# main.net
KiCad netlist of a schematic drawn in EAGLE
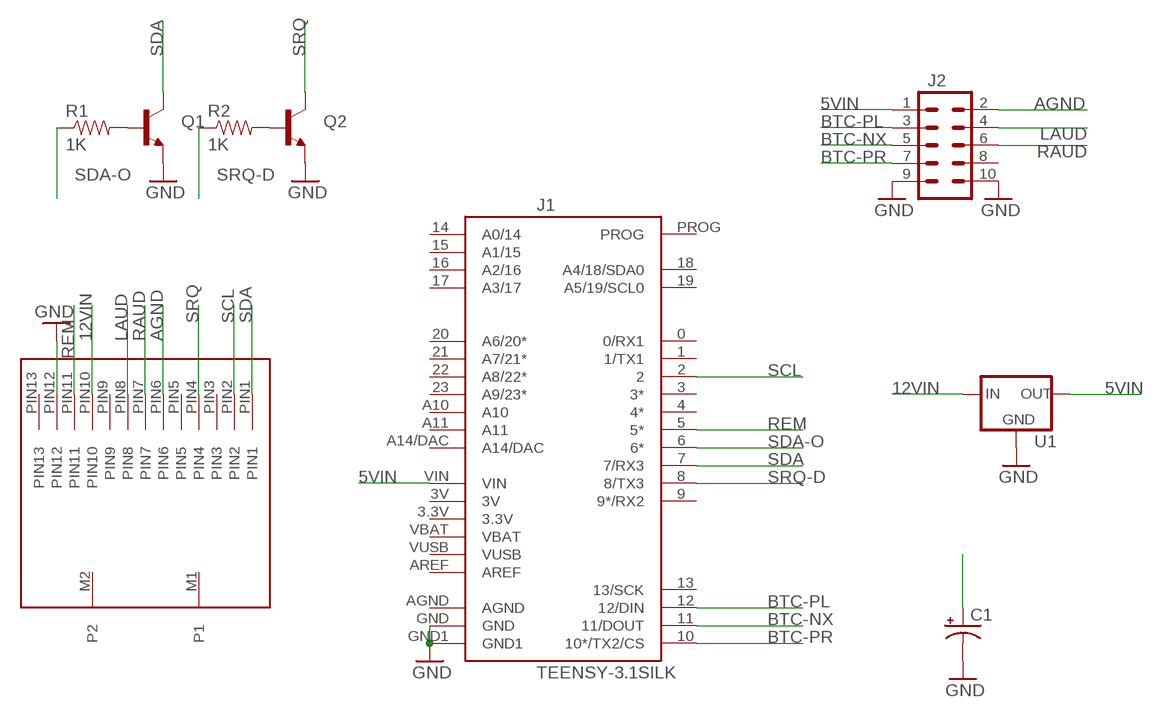
[diagram p0: schematic, sheet 1]

(export (version "E")
  (design (tool "Eeschema 10.0.6"))
  (components
    (comp (ref "C1")
      (value "10UF-25V-20%(PTH)")
      (footprint "eagle-import:CPOL-RADIAL-10UF-25V")
      (libsource (lib "eagle-import") (part "10UF-25V-20%(PTH)"))
    )
    (comp (ref "J1")
      (value "TEENSY-3.1SILK")
      (footprint "eagle-import:TEENSY-3.1")
      (libsource (lib "eagle-import") (part "TEENSY-3.1SILK"))
    )
    (comp (ref "J2")
      (value "M05X2NO_SILK")
      (footprint "eagle-import:2X5_NOSILK")
      (libsource (lib "eagle-import") (part "M05X2NO_SILK"))
    )
    (comp (ref "Q1")
      (value "TRANSISTOR_NPN2N3904")
      (footprint "eagle-import:TO-92")
      (libsource (lib "eagle-import") (part "TRANSISTOR_NPN2N3904"))
    )
    (comp (ref "Q2")
      (value "TRANSISTOR_NPN2N3904")
      (footprint "eagle-import:TO-92")
      (libsource (lib "eagle-import") (part "TRANSISTOR_NPN2N3904"))
    )
    (comp (ref "R1")
      (value "1K")
      (footprint "eagle-import:AXIAL-0.3")
      (libsource (lib "eagle-import") (part "1KOHM-1/4W-1%(PTH)"))
    )
    (comp (ref "R2")
      (value "1K")
      (footprint "eagle-import:AXIAL-0.3")
      (libsource (lib "eagle-import") (part "1KOHM-1/4W-1%(PTH)"))
    )
    (comp (ref "U$1")
      (value "13-DIN13PINDIN")
      (footprint "eagle-import:DIN-13")
      (libsource (lib "eagle-import") (part "13-DIN13PINDIN"))
    )
    (comp (ref "U1")
      (value "V_REG_78XX-TO-220")
      (footprint "eagle-import:TO-220-ALT")
      (libsource (lib "eagle-import") (part "V_REG_78XX-TO-220"))
    )
  )
  (nets
    (net (code "1") (name "/5VIN") (class "Default")
      (node (ref "C1") (pin "1") (pinfunction "+_1") (pintype "passive"))
      (node (ref "J1") (pin "VIN") (pinfunction "VIN_VIN") (pintype "bidirectional"))
      (node (ref "J2") (pin "1") (pinfunction "1_1") (pintype "passive"))
      (node (ref "U1") (pin "OUT") (pinfunction "OUT_OUT") (pintype "passive"))
    )
    (net (code "2") (name "/12VIN") (class "Default")
      (node (ref "U$1") (pin "PIN10") (pinfunction "PIN10_PIN10") (pintype "bidirectional"))
      (node (ref "U1") (pin "IN") (pinfunction "IN_IN") (pintype "input"))
    )
    (net (code "3") (name "/AGND") (class "Default")
      (node (ref "J2") (pin "2") (pinfunction "2_2") (pintype "passive"))
      (node (ref "U$1") (pin "PIN6") (pinfunction "PIN6_PIN6") (pintype "bidirectional"))
    )
    (net (code "4") (name "/BTC-NX") (class "Default")
      (node (ref "J1") (pin "11") (pinfunction "11/DOUT_11") (pintype "bidirectional"))
      (node (ref "J2") (pin "5") (pinfunction "5_5") (pintype "passive"))
    )
    (net (code "5") (name "/BTC-PL") (class "Default")
      (node (ref "J1") (pin "12") (pinfunction "12/DIN_12") (pintype "bidirectional"))
      (node (ref "J2") (pin "3") (pinfunction "3_3") (pintype "passive"))
    )
    (net (code "6") (name "/BTC-PR") (class "Default")
      (node (ref "J1") (pin "10") (pinfunction "10*/TX2/CS_10") (pintype "bidirectional"))
      (node (ref "J2") (pin "7") (pinfunction "7_7") (pintype "passive"))
    )
    (net (code "7") (name "/LAUD") (class "Default")
      (node (ref "J2") (pin "4") (pinfunction "4_4") (pintype "passive"))
      (node (ref "U$1") (pin "PIN8") (pinfunction "PIN8_PIN8") (pintype "bidirectional"))
    )
    (net (code "8") (name "/RAUD") (class "Default")
      (node (ref "J2") (pin "6") (pinfunction "6_6") (pintype "passive"))
      (node (ref "U$1") (pin "PIN7") (pinfunction "PIN7_PIN7") (pintype "bidirectional"))
    )
    (net (code "9") (name "/REM") (class "Default")
      (node (ref "J1") (pin "5") (pinfunction "5*_5") (pintype "bidirectional"))
      (node (ref "U$1") (pin "PIN11") (pinfunction "PIN11_PIN11") (pintype "bidirectional"))
    )
    (net (code "10") (name "/SCL") (class "Default")
      (node (ref "J1") (pin "2") (pinfunction "2_2") (pintype "bidirectional"))
      (node (ref "U$1") (pin "PIN2") (pinfunction "PIN2_PIN2") (pintype "bidirectional"))
    )
    (net (code "11") (name "/SDA") (class "Default")
      (node (ref "J1") (pin "7") (pinfunction "7/RX3_7") (pintype "bidirectional"))
      (node (ref "Q1") (pin "3") (pinfunction "C_3") (pintype "passive"))
      (node (ref "U$1") (pin "PIN1") (pinfunction "PIN1_PIN1") (pintype "bidirectional"))
    )
    (net (code "12") (name "/SDA-O") (class "Default")
      (node (ref "J1") (pin "6") (pinfunction "6*_6") (pintype "bidirectional"))
      (node (ref "R1") (pin "P$1") (pinfunction "1_P$1") (pintype "passive"))
    )
    (net (code "13") (name "/SRQ") (class "Default")
      (node (ref "Q2") (pin "3") (pinfunction "C_3") (pintype "passive"))
      (node (ref "U$1") (pin "PIN4") (pinfunction "PIN4_PIN4") (pintype "bidirectional"))
    )
    (net (code "14") (name "/SRQ-D") (class "Default")
      (node (ref "J1") (pin "8") (pinfunction "8/TX3_8") (pintype "bidirectional"))
      (node (ref "R2") (pin "P$1") (pinfunction "1_P$1") (pintype "passive"))
    )
    (net (code "15") (name "GND") (class "Default")
      (node (ref "C1") (pin "2") (pinfunction "-_2") (pintype "passive"))
      (node (ref "J1") (pin "GND") (pinfunction "GND_GND") (pintype "bidirectional"))
      (node (ref "J1") (pin "GND1") (pinfunction "GND1_GND1") (pintype "bidirectional"))
      (node (ref "J2") (pin "10") (pinfunction "10_10") (pintype "passive"))
      (node (ref "J2") (pin "9") (pinfunction "9_9") (pintype "passive"))
      (node (ref "Q1") (pin "1") (pinfunction "E_1") (pintype "passive"))
      (node (ref "Q2") (pin "1") (pinfunction "E_1") (pintype "passive"))
      (node (ref "U$1") (pin "PIN12") (pinfunction "PIN12_PIN12") (pintype "bidirectional"))
      (node (ref "U1") (pin "GND") (pinfunction "GND_GND") (pintype "input"))
    )
    (net (code "16") (name "Net-(Q1-B)") (class "Default")
      (node (ref "Q1") (pin "2") (pinfunction "B_2") (pintype "passive"))
      (node (ref "R1") (pin "P$2") (pinfunction "2_P$2") (pintype "passive"))
    )
    (net (code "17") (name "Net-(Q2-B)") (class "Default")
      (node (ref "Q2") (pin "2") (pinfunction "B_2") (pintype "passive"))
      (node (ref "R2") (pin "P$2") (pinfunction "2_P$2") (pintype "passive"))
    )
    (net (code "18") (name "unconnected-(J1-0{slash}RX1-Pad0)") (class "Default")
      (node (ref "J1") (pin "0") (pinfunction "0/RX1_0") (pintype "bidirectional"))
    )
    (net (code "19") (name "unconnected-(J1-1{slash}TX1-Pad1)") (class "Default")
      (node (ref "J1") (pin "1") (pinfunction "1/TX1_1") (pintype "bidirectional"))
    )
    (net (code "20") (name "unconnected-(J1-3*-Pad3)") (class "Default")
      (node (ref "J1") (pin "3") (pinfunction "3*_3") (pintype "bidirectional"))
    )
    (net (code "21") (name "unconnected-(J1-4*-Pad4)") (class "Default")
      (node (ref "J1") (pin "4") (pinfunction "4*_4") (pintype "bidirectional"))
    )
    (net (code "22") (name "unconnected-(J1-9*{slash}RX2-Pad9)") (class "Default")
      (node (ref "J1") (pin "9") (pinfunction "9*/RX2_9") (pintype "bidirectional"))
    )
    (net (code "23") (name "unconnected-(J1-13{slash}SCK-Pad13)") (class "Default")
      (node (ref "J1") (pin "13") (pinfunction "13/SCK_13") (pintype "bidirectional"))
    )
    (net (code "24") (name "unconnected-(J1-A0{slash}14-Pad14)") (class "Default")
      (node (ref "J1") (pin "14") (pinfunction "A0/14_14") (pintype "bidirectional"))
    )
    (net (code "25") (name "unconnected-(J1-A1{slash}15-Pad15)") (class "Default")
      (node (ref "J1") (pin "15") (pinfunction "A1/15_15") (pintype "bidirectional"))
    )
    (net (code "26") (name "unconnected-(J1-A2{slash}16-Pad16)") (class "Default")
      (node (ref "J1") (pin "16") (pinfunction "A2/16_16") (pintype "bidirectional"))
    )
    (net (code "27") (name "unconnected-(J1-A3{slash}17-Pad17)") (class "Default")
      (node (ref "J1") (pin "17") (pinfunction "A3/17_17") (pintype "bidirectional"))
    )
    (net (code "28") (name "unconnected-(J1-A4{slash}18{slash}SDA0-Pad18)") (class "Default")
      (node (ref "J1") (pin "18") (pinfunction "A4/18/SDA0_18") (pintype "bidirectional"))
    )
    (net (code "29") (name "unconnected-(J1-A5{slash}19{slash}SCL0-Pad19)") (class "Default")
      (node (ref "J1") (pin "19") (pinfunction "A5/19/SCL0_19") (pintype "bidirectional"))
    )
    (net (code "30") (name "unconnected-(J1-A6{slash}20*-Pad20)") (class "Default")
      (node (ref "J1") (pin "20") (pinfunction "A6/20*_20") (pintype "bidirectional"))
    )
    (net (code "31") (name "unconnected-(J1-A7{slash}21*-Pad21)") (class "Default")
      (node (ref "J1") (pin "21") (pinfunction "A7/21*_21") (pintype "bidirectional"))
    )
    (net (code "32") (name "unconnected-(J1-A8{slash}22*-Pad22)") (class "Default")
      (node (ref "J1") (pin "22") (pinfunction "A8/22*_22") (pintype "bidirectional"))
    )
    (net (code "33") (name "unconnected-(J1-A9{slash}23*-Pad23)") (class "Default")
      (node (ref "J1") (pin "23") (pinfunction "A9/23*_23") (pintype "bidirectional"))
    )
    (net (code "34") (name "unconnected-(J1-Pad3.3V)") (class "Default")
      (node (ref "J1") (pin "3.3V") (pinfunction "3.3V_3.3V") (pintype "bidirectional"))
    )
    (net (code "35") (name "unconnected-(J1-Pad3V)") (class "Default")
      (node (ref "J1") (pin "3V") (pinfunction "3V_3V") (pintype "bidirectional"))
    )
    (net (code "36") (name "unconnected-(J1-PadA10)") (class "Default")
      (node (ref "J1") (pin "A10") (pinfunction "A10_A10") (pintype "bidirectional"))
    )
    (net (code "37") (name "unconnected-(J1-PadA11)") (class "Default")
      (node (ref "J1") (pin "A11") (pinfunction "A11_A11") (pintype "bidirectional"))
    )
    (net (code "38") (name "unconnected-(J1-PadA14{slash}DAC)") (class "Default")
      (node (ref "J1") (pin "A14/DAC") (pinfunction "A14/DAC_A14/DAC") (pintype "bidirectional"))
    )
    (net (code "39") (name "unconnected-(J1-PadAGND)") (class "Default")
      (node (ref "J1") (pin "AGND") (pinfunction "AGND_AGND") (pintype "bidirectional"))
    )
    (net (code "40") (name "unconnected-(J1-PadAREF)") (class "Default")
      (node (ref "J1") (pin "AREF") (pinfunction "AREF_AREF") (pintype "bidirectional"))
    )
    (net (code "41") (name "unconnected-(J1-PadPROG)") (class "Default")
      (node (ref "J1") (pin "PROG") (pinfunction "PROG_PROG") (pintype "bidirectional"))
    )
    (net (code "42") (name "unconnected-(J1-PadVBAT)") (class "Default")
      (node (ref "J1") (pin "VBAT") (pinfunction "VBAT_VBAT") (pintype "bidirectional"))
    )
    (net (code "43") (name "unconnected-(J1-PadVUSB)") (class "Default")
      (node (ref "J1") (pin "VUSB") (pinfunction "VUSB_VUSB") (pintype "bidirectional"))
    )
    (net (code "44") (name "unconnected-(J2-Pad8)") (class "Default")
      (node (ref "J2") (pin "8") (pinfunction "8_8") (pintype "passive"))
    )
    (net (code "45") (name "unconnected-(U$1-P1-PadM1)") (class "Default")
      (node (ref "U$1") (pin "M1") (pinfunction "P1_M1") (pintype "bidirectional"))
    )
    (net (code "46") (name "unconnected-(U$1-P2-PadM2)") (class "Default")
      (node (ref "U$1") (pin "M2") (pinfunction "P2_M2") (pintype "bidirectional"))
    )
    (net (code "47") (name "unconnected-(U$1-PadPIN3)") (class "Default")
      (node (ref "U$1") (pin "PIN3") (pinfunction "PIN3_PIN3") (pintype "bidirectional"))
    )
    (net (code "48") (name "unconnected-(U$1-PadPIN5)") (class "Default")
      (node (ref "U$1") (pin "PIN5") (pinfunction "PIN5_PIN5") (pintype "bidirectional"))
    )
    (net (code "49") (name "unconnected-(U$1-PadPIN9)") (class "Default")
      (node (ref "U$1") (pin "PIN9") (pinfunction "PIN9_PIN9") (pintype "bidirectional"))
    )
    (net (code "50") (name "unconnected-(U$1-PadPIN13)") (class "Default")
      (node (ref "U$1") (pin "PIN13") (pinfunction "PIN13_PIN13") (pintype "bidirectional"))
    )
  )
)
